# jlink-ob.net
KiCad netlist of a schematic drawn in Altium Designer
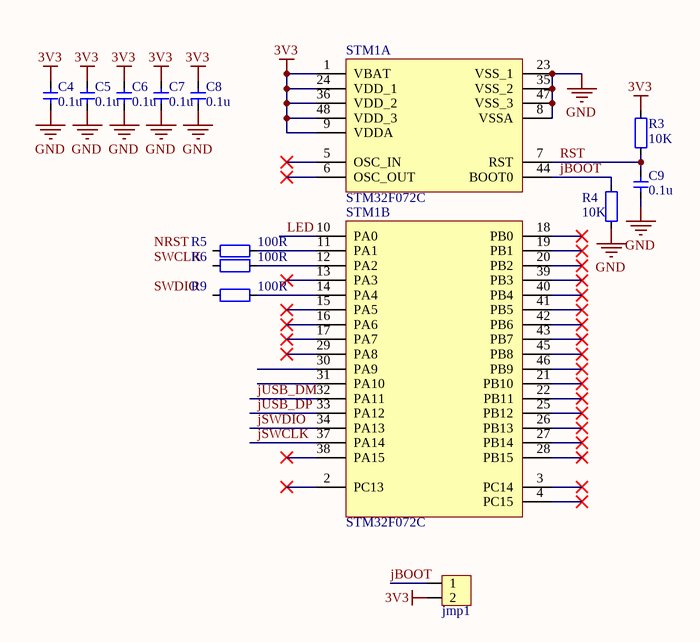
[diagram p0: jlink-ob.SchDoc]

(export (version "E")
  (design (tool "Eeschema 10.0.6"))
  (components
    (comp (ref "C4")
      (value "0.1u")
      (footprint "PCB_PassiveCap:CAP_0603")
      (description "Capacitor")
      (fields (field (name "Comment") "Cap_0603"))
      (libsource (lib "SCH_Passive") (part "Cap_0603"))
    )
    (comp (ref "C5")
      (value "0.1u")
      (footprint "PCB_PassiveCap:CAP_0603")
      (description "Capacitor")
      (fields (field (name "Comment") "Cap_0603"))
      (libsource (lib "SCH_Passive") (part "Cap_0603"))
    )
    (comp (ref "C6")
      (value "0.1u")
      (footprint "PCB_PassiveCap:CAP_0603")
      (description "Capacitor")
      (fields (field (name "Comment") "Cap_0603"))
      (libsource (lib "SCH_Passive") (part "Cap_0603"))
    )
    (comp (ref "C7")
      (value "0.1u")
      (footprint "PCB_PassiveCap:CAP_0603")
      (description "Capacitor")
      (fields (field (name "Comment") "Cap_0603"))
      (libsource (lib "SCH_Passive") (part "Cap_0603"))
    )
    (comp (ref "C8")
      (value "0.1u")
      (footprint "PCB_PassiveCap:CAP_0603")
      (description "Capacitor")
      (fields (field (name "Comment") "Cap_0603"))
      (libsource (lib "SCH_Passive") (part "Cap_0603"))
    )
    (comp (ref "C9")
      (value "0.1u")
      (footprint "PCB_PassiveCap:CAP_0603")
      (description "Capacitor")
      (fields (field (name "Comment") "Cap_0603"))
      (libsource (lib "SCH_Passive") (part "Cap_0603"))
    )
    (comp (ref "jmp1")
      (value "HDR1x2_2.54")
      (footprint "PCB_ConnectorHDR:HDR1X2_2.54_180")
      (description "Header")
      (libsource (lib "SCH_ConnectorHDR") (part "HDR1x2_2.54"))
    )
    (comp (ref "R3")
      (value "10K")
      (footprint "PCB_PassiveRes:RES_0603")
      (description "Resistor")
      (fields (field (name "Comment") "Res_0603"))
      (libsource (lib "SCH_Passive") (part "Res_0603"))
    )
    (comp (ref "R4")
      (value "10K")
      (footprint "PCB_PassiveRes:RES_0603")
      (description "Resistor")
      (fields (field (name "Comment") "Res_0603"))
      (libsource (lib "SCH_Passive") (part "Res_0603"))
    )
    (comp (ref "R5")
      (value "100R")
      (footprint "PCB_PassiveRes:RES_0603")
      (description "Resistor")
      (fields (field (name "Comment") "Res_0603"))
      (libsource (lib "") (part "Res_0603_1"))
    )
    (comp (ref "R6")
      (value "100R")
      (footprint "PCB_PassiveRes:RES_0603")
      (description "Resistor")
      (fields (field (name "Comment") "Res_0603"))
      (libsource (lib "") (part "Res_0603_1"))
    )
    (comp (ref "R9")
      (value "100R")
      (footprint "PCB_PassiveRes:RES_0603")
      (description "Resistor")
      (fields (field (name "Comment") "Res_0603"))
      (libsource (lib "") (part "Res_0603_1"))
    )
    (comp (ref "STM1")
      (value "STM32F072C")
      (footprint "PCB_IntegratedCircuit:LQFP_P0.5_48")
      (description "MCU")
      (libsource (lib "SCH_IntegratedCircuit") (part "STM32F103C"))
    )
  )
  (nets
    (net (code "1") (name "/LED") (class "Default")
      (node (ref "STM1") (pin "10") (pinfunction "PA0_10") (pintype "passive"))
    )
    (net (code "3") (name "/RST") (class "Default")
      (node (ref "C9") (pin "2") (pinfunction "2_2") (pintype "passive"))
      (node (ref "R3") (pin "1") (pinfunction "1_1") (pintype "passive"))
      (node (ref "STM1") (pin "7") (pinfunction "RST_7") (pintype "passive"))
    )
    (net (code "6") (name "/jBOOT") (class "Default")
      (node (ref "R4") (pin "2") (pinfunction "2_2") (pintype "passive"))
      (node (ref "STM1") (pin "44") (pinfunction "BOOT0_44") (pintype "passive"))
      (node (ref "jmp1") (pin "1") (pinfunction "1_1") (pintype "passive"))
    )
    (net (code "7") (name "/jSWCLK") (class "Default")
      (node (ref "STM1") (pin "37") (pinfunction "PA14_37") (pintype "passive"))
    )
    (net (code "8") (name "/jSWDIO") (class "Default")
      (node (ref "STM1") (pin "34") (pinfunction "PA13_34") (pintype "passive"))
    )
    (net (code "9") (name "/jUSB_DM") (class "Default")
      (node (ref "STM1") (pin "32") (pinfunction "PA11_32") (pintype "passive"))
    )
    (net (code "10") (name "/jUSB_DP") (class "Default")
      (node (ref "STM1") (pin "33") (pinfunction "PA12_33") (pintype "passive"))
    )
    (net (code "11") (name "3V3") (class "Default")
      (node (ref "C4") (pin "1") (pinfunction "1_1") (pintype "passive"))
      (node (ref "C5") (pin "1") (pinfunction "1_1") (pintype "passive"))
      (node (ref "C6") (pin "1") (pinfunction "1_1") (pintype "passive"))
      (node (ref "C7") (pin "1") (pinfunction "1_1") (pintype "passive"))
      (node (ref "C8") (pin "2") (pinfunction "2_2") (pintype "passive"))
      (node (ref "R3") (pin "2") (pinfunction "2_2") (pintype "passive"))
      (node (ref "STM1") (pin "1") (pinfunction "VBAT_1") (pintype "passive"))
      (node (ref "STM1") (pin "24") (pinfunction "VDD_1_24") (pintype "passive"))
      (node (ref "STM1") (pin "36") (pinfunction "VDD_2_36") (pintype "passive"))
      (node (ref "STM1") (pin "48") (pinfunction "VDD_3_48") (pintype "passive"))
      (node (ref "STM1") (pin "9") (pinfunction "VDDA_9") (pintype "passive"))
      (node (ref "jmp1") (pin "2") (pinfunction "2_2") (pintype "passive"))
    )
    (net (code "12") (name "GND") (class "Default")
      (node (ref "C4") (pin "2") (pinfunction "2_2") (pintype "passive"))
      (node (ref "C5") (pin "2") (pinfunction "2_2") (pintype "passive"))
      (node (ref "C6") (pin "2") (pinfunction "2_2") (pintype "passive"))
      (node (ref "C7") (pin "2") (pinfunction "2_2") (pintype "passive"))
      (node (ref "C8") (pin "1") (pinfunction "1_1") (pintype "passive"))
      (node (ref "C9") (pin "1") (pinfunction "1_1") (pintype "passive"))
      (node (ref "R4") (pin "1") (pinfunction "1_1") (pintype "passive"))
      (node (ref "STM1") (pin "23") (pinfunction "VSS_1_23") (pintype "passive"))
      (node (ref "STM1") (pin "35") (pinfunction "VSS_2_35") (pintype "passive"))
      (node (ref "STM1") (pin "47") (pinfunction "VSS_3_47") (pintype "passive"))
      (node (ref "STM1") (pin "8") (pinfunction "VSSA_8") (pintype "passive"))
    )
    (net (code "13") (name "Net-(STM1B-PA1)") (class "Default")
      (node (ref "R5") (pin "2") (pinfunction "2_2") (pintype "passive"))
      (node (ref "STM1") (pin "11") (pinfunction "PA1_11") (pintype "passive"))
    )
    (net (code "14") (name "Net-(STM1B-PA2)") (class "Default")
      (node (ref "R6") (pin "2") (pinfunction "2_2") (pintype "passive"))
      (node (ref "STM1") (pin "12") (pinfunction "PA2_12") (pintype "passive"))
    )
    (net (code "15") (name "Net-(STM1B-PA4)") (class "Default")
      (node (ref "R9") (pin "2") (pinfunction "2_2") (pintype "passive"))
      (node (ref "STM1") (pin "14") (pinfunction "PA4_14") (pintype "passive"))
    )
    (net (code "16") (name "unconnected-(R5-Pad1)") (class "Default")
      (node (ref "R5") (pin "1") (pinfunction "1_1") (pintype "passive"))
    )
    (net (code "17") (name "unconnected-(R6-Pad1)") (class "Default")
      (node (ref "R6") (pin "1") (pinfunction "1_1") (pintype "passive"))
    )
    (net (code "18") (name "unconnected-(R9-Pad1)") (class "Default")
      (node (ref "R9") (pin "1") (pinfunction "1_1") (pintype "passive"))
    )
    (net (code "19") (name "unconnected-(STM1A-OSC_IN-Pad5)") (class "Default")
      (node (ref "STM1") (pin "5") (pinfunction "OSC_IN_5") (pintype "passive+no_connect"))
    )
    (net (code "20") (name "unconnected-(STM1A-OSC_OUT-Pad6)") (class "Default")
      (node (ref "STM1") (pin "6") (pinfunction "OSC_OUT_6") (pintype "passive+no_connect"))
    )
    (net (code "21") (name "unconnected-(STM1B-PA3-Pad13)") (class "Default")
      (node (ref "STM1") (pin "13") (pinfunction "PA3_13") (pintype "passive+no_connect"))
    )
    (net (code "22") (name "unconnected-(STM1B-PA5-Pad15)") (class "Default")
      (node (ref "STM1") (pin "15") (pinfunction "PA5_15") (pintype "passive+no_connect"))
    )
    (net (code "23") (name "unconnected-(STM1B-PA6-Pad16)") (class "Default")
      (node (ref "STM1") (pin "16") (pinfunction "PA6_16") (pintype "passive+no_connect"))
    )
    (net (code "24") (name "unconnected-(STM1B-PA7-Pad17)") (class "Default")
      (node (ref "STM1") (pin "17") (pinfunction "PA7_17") (pintype "passive+no_connect"))
    )
    (net (code "25") (name "unconnected-(STM1B-PA8-Pad29)") (class "Default")
      (node (ref "STM1") (pin "29") (pinfunction "PA8_29") (pintype "passive+no_connect"))
    )
    (net (code "26") (name "unconnected-(STM1B-PA9-Pad30)") (class "Default")
      (node (ref "STM1") (pin "30") (pinfunction "PA9_30") (pintype "passive"))
    )
    (net (code "27") (name "unconnected-(STM1B-PA10-Pad31)") (class "Default")
      (node (ref "STM1") (pin "31") (pinfunction "PA10_31") (pintype "passive"))
    )
    (net (code "28") (name "unconnected-(STM1B-PA15-Pad38)") (class "Default")
      (node (ref "STM1") (pin "38") (pinfunction "PA15_38") (pintype "passive+no_connect"))
    )
    (net (code "29") (name "unconnected-(STM1B-PB0-Pad18)") (class "Default")
      (node (ref "STM1") (pin "18") (pinfunction "PB0_18") (pintype "passive+no_connect"))
    )
    (net (code "30") (name "unconnected-(STM1B-PB1-Pad19)") (class "Default")
      (node (ref "STM1") (pin "19") (pinfunction "PB1_19") (pintype "passive+no_connect"))
    )
    (net (code "31") (name "unconnected-(STM1B-PB2-Pad20)") (class "Default")
      (node (ref "STM1") (pin "20") (pinfunction "PB2_20") (pintype "passive+no_connect"))
    )
    (net (code "32") (name "unconnected-(STM1B-PB3-Pad39)") (class "Default")
      (node (ref "STM1") (pin "39") (pinfunction "PB3_39") (pintype "passive+no_connect"))
    )
    (net (code "33") (name "unconnected-(STM1B-PB4-Pad40)") (class "Default")
      (node (ref "STM1") (pin "40") (pinfunction "PB4_40") (pintype "passive+no_connect"))
    )
    (net (code "34") (name "unconnected-(STM1B-PB5-Pad41)") (class "Default")
      (node (ref "STM1") (pin "41") (pinfunction "PB5_41") (pintype "passive+no_connect"))
    )
    (net (code "35") (name "unconnected-(STM1B-PB6-Pad42)") (class "Default")
      (node (ref "STM1") (pin "42") (pinfunction "PB6_42") (pintype "passive+no_connect"))
    )
    (net (code "36") (name "unconnected-(STM1B-PB7-Pad43)") (class "Default")
      (node (ref "STM1") (pin "43") (pinfunction "PB7_43") (pintype "passive+no_connect"))
    )
    (net (code "37") (name "unconnected-(STM1B-PB8-Pad45)") (class "Default")
      (node (ref "STM1") (pin "45") (pinfunction "PB8_45") (pintype "passive+no_connect"))
    )
    (net (code "38") (name "unconnected-(STM1B-PB9-Pad46)") (class "Default")
      (node (ref "STM1") (pin "46") (pinfunction "PB9_46") (pintype "passive+no_connect"))
    )
    (net (code "39") (name "unconnected-(STM1B-PB10-Pad21)") (class "Default")
      (node (ref "STM1") (pin "21") (pinfunction "PB10_21") (pintype "passive+no_connect"))
    )
    (net (code "40") (name "unconnected-(STM1B-PB11-Pad22)") (class "Default")
      (node (ref "STM1") (pin "22") (pinfunction "PB11_22") (pintype "passive+no_connect"))
    )
    (net (code "41") (name "unconnected-(STM1B-PB12-Pad25)") (class "Default")
      (node (ref "STM1") (pin "25") (pinfunction "PB12_25") (pintype "passive+no_connect"))
    )
    (net (code "42") (name "unconnected-(STM1B-PB13-Pad26)") (class "Default")
      (node (ref "STM1") (pin "26") (pinfunction "PB13_26") (pintype "passive+no_connect"))
    )
    (net (code "43") (name "unconnected-(STM1B-PB14-Pad27)") (class "Default")
      (node (ref "STM1") (pin "27") (pinfunction "PB14_27") (pintype "passive+no_connect"))
    )
    (net (code "44") (name "unconnected-(STM1B-PB15-Pad28)") (class "Default")
      (node (ref "STM1") (pin "28") (pinfunction "PB15_28") (pintype "passive+no_connect"))
    )
    (net (code "45") (name "unconnected-(STM1B-PC13-Pad2)") (class "Default")
      (node (ref "STM1") (pin "2") (pinfunction "PC13_2") (pintype "passive+no_connect"))
    )
    (net (code "46") (name "unconnected-(STM1B-PC14-Pad3)") (class "Default")
      (node (ref "STM1") (pin "3") (pinfunction "PC14_3") (pintype "passive+no_connect"))
    )
    (net (code "47") (name "unconnected-(STM1B-PC15-Pad4)") (class "Default")
      (node (ref "STM1") (pin "4") (pinfunction "PC15_4") (pintype "passive+no_connect"))
    )
  )
)
